# JacdacRHTemp_18.net
KiCad netlist of a schematic drawn in Altium Designer
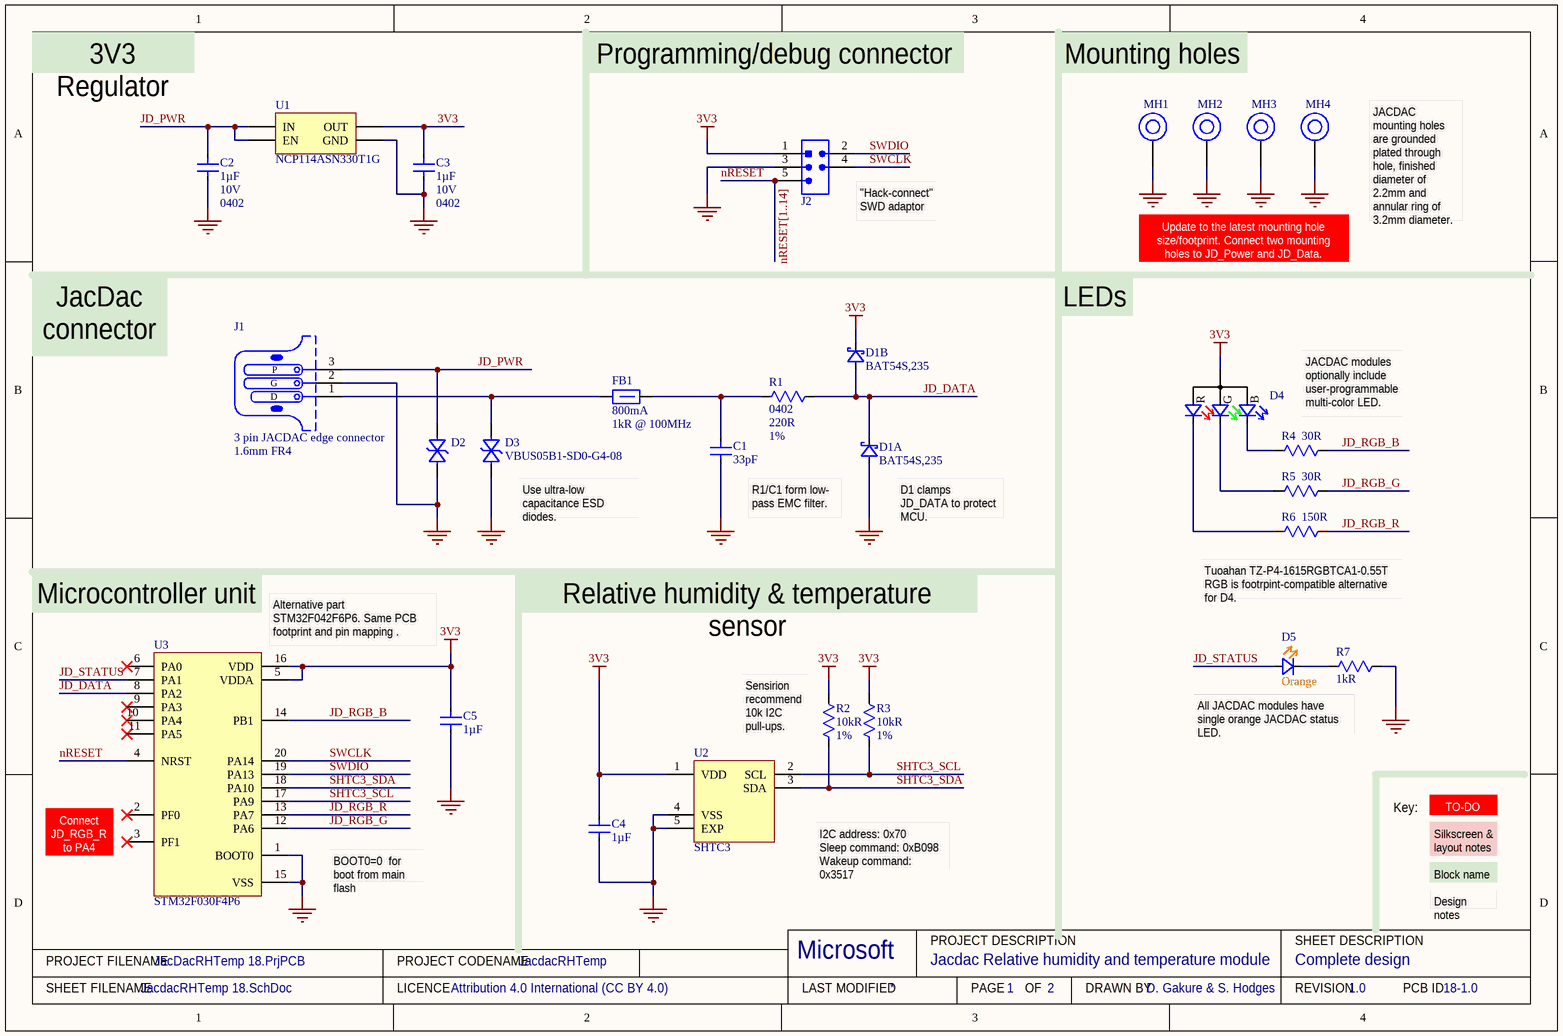
[diagram p0: JacdacRHTemp 18.SchDoc]

(export (version "E")
  (design (tool "Eeschema 10.0.6"))
  (components
    (comp (ref "C1")
      (value "CL05C330JB51PNC")
      (footprint "C0402_0.55MM - without outline")
      (description "CAP CER 33PF 50V NP0 0402")
      (fields
        (field (name "MANUFACTURER") "Samsung")
        (field (name "TOLERANCE") "5%")
        (field (name "CAPACITANCE") "33pF")
        (field (name "CHECKED") "?")
        (field (name "CREATED") "DG")
      )
      (libsource (lib "Samsung") (part "CL05C330JB51PNC"))
    )
    (comp (ref "C2")
      (value "CL05A105KP5NNNC")
      (footprint "C0402_0.55MM - without outline")
      (description "CAP CER 1UF 10V X5R 0402")
      (fields
        (field (name "MANUFACTURER") "Samsung")
        (field (name "TOLERANCE") "10%")
        (field (name "CAPACITANCE") "1µF")
        (field (name "VOLTAGE RATING") "10V")
        (field (name "CASE CODE (IMPERIAL)") "0402")
        (field (name "CREATED") "DG")
        (field (name "CHECKED") "?")
      )
      (libsource (lib "Samsung") (part "CL05A105KP5NNNC"))
    )
    (comp (ref "C3")
      (value "CL05A105KP5NNNC")
      (footprint "C0402_0.55MM - without outline")
      (description "CAP CER 1UF 10V X5R 0402")
      (fields
        (field (name "MANUFACTURER") "Samsung")
        (field (name "TOLERANCE") "10%")
        (field (name "CAPACITANCE") "1µF")
        (field (name "VOLTAGE RATING") "10V")
        (field (name "CASE CODE (IMPERIAL)") "0402")
        (field (name "CREATED") "DG")
        (field (name "CHECKED") "?")
      )
      (libsource (lib "Samsung") (part "CL05A105KP5NNNC"))
    )
    (comp (ref "C4")
      (value "CL05A105KP5NNNC")
      (footprint "C0402_0.55MM - without outline")
      (description "CAP CER 1UF 10V X5R 0402")
      (fields
        (field (name "MANUFACTURER") "Samsung")
        (field (name "TOLERANCE") "10%")
        (field (name "CAPACITANCE") "1µF")
        (field (name "CREATED") "DG")
        (field (name "CHECKED") "?")
      )
      (libsource (lib "Samsung") (part "CL05A105KP5NNNC"))
    )
    (comp (ref "C5")
      (value "CL05A105KP5NNNC")
      (footprint "C0402_0.55MM - without outline")
      (description "CAP CER 1UF 10V X5R 0402")
      (fields
        (field (name "MANUFACTURER") "Samsung")
        (field (name "TOLERANCE") "10%")
        (field (name "CAPACITANCE") "1µF")
        (field (name "CREATED") "DG")
        (field (name "CHECKED") "?")
      )
      (libsource (lib "Samsung") (part "CL05A105KP5NNNC"))
    )
    (comp (ref "D1")
      (value "BAT54S")
      (footprint "NXP-BAT54S-TO-236AB")
      (description "DIODE ARRAY SCHOTTKY 30V SOT23")
      (fields (field (name "MANUFACTURER") "Nexperia") (field (name "MANUFACTURER PART NUMBER") "BAT54S,235"))
      (libsource (lib "NXP") (part "BAT54S"))
    )
    (comp (ref "D2")
      (value "VBUS05B1-SD0-G4-08")
      (footprint "0201-VBUS05B1-SD0-G4-08 - Without outline")
      (description "TVS DIODE 5.5V 18V CLP0603")
      (fields
        (field (name "MANUFACTURER") "Vishay Semiconductors")
        (field (name "CREATED BY") "D. Gakure")
        (field (name "CHECKED BY") "?")
      )
      (libsource (lib "Vishay") (part "VBUS05B1-SD0-G4-08"))
    )
    (comp (ref "D3")
      (value "VBUS05B1-SD0-G4-08")
      (footprint "0201-VBUS05B1-SD0-G4-08 - Without outline")
      (description "TVS DIODE 5.5V 18V CLP0603")
      (fields
        (field (name "MANUFACTURER") "Vishay Semiconductors")
        (field (name "MANUFACTURER PART NUMBER") "VBUS05B1-SD0-G4-08")
        (field (name "CREATED BY") "D. Gakure")
        (field (name "CHECKED BY") "?")
      )
      (libsource (lib "Vishay") (part "VBUS05B1-SD0-G4-08"))
    )
    (comp (ref "D4")
      (value "HSMF-C114")
      (footprint "HSMF-C114")
      (fields
        (field (name "MANUFACTURER") "Broadcom Avago")
        (field (name "CREATED BY") "D. Gakure")
        (field (name "CHECKED BY") "?")
      )
      (libsource (lib "BroadcomLimited") (part "HSMF-C114"))
    )
    (comp (ref "D5")
      (value "SML-D12D")
      (footprint "Rohm SML-D12 Orange - without outline")
      (description "1.6 x 0.8 x 0.55mm (0603) LED 605nm Orange")
      (fields
        (field (name "MANUFACTURER") "Rohm Semiconductor")
        (field (name "MANUFACTURER PART NUMBER") "SML-D12D8WT86")
        (field (name "COLOUR") "Orange")
      )
      (libsource (lib "Rohm") (part "SML-D12D"))
    )
    (comp (ref "FB1")
      (value "TDK MPZ1608S102ATA00")
      (footprint "TDK MPZ1608 0.8mm - without outline")
      (description "0603 1k@100MHz 0.8A chip")
      (fields
        (field (name "TOLERANCE") "25%")
        (field (name "MANUFACTURER") "TDK")
        (field (name "CURRENT RATING") "800mA")
        (field (name "IMPEDANCE") "1kR @ 100MHz")
      )
      (libsource (lib "TDK") (part "TDK MPZ1608S102ATA00"))
    )
    (comp (ref "J1")
      (value "3 pin JACDAC edge connector")
      (footprint "JACDAC_EDGE_CONNECTOR_9.15MM_PCB_WIDE _without_MH")
      (description "3 pin JACDAC edge connector 1.27mm pitch")
      (fields
        (field (name "MANUFACTURER PART NUMBER") "JACDAC_EDGE_CONNECTOR")
        (field (name "PCB TYPE") "1.6mm FR4")
        (field (name "CHECKED BY") "?")
        (field (name "CREATED BY") "D. Gakure")
      )
      (libsource (lib "generic-con") (part "JACDAC edge connector"))
    )
    (comp (ref "J2")
      (value "Hack Connect Mini 1.27 mm pitch 2-row")
      (footprint "HACK_CONNECT_MINI_5_X_1_27")
      (libsource (lib "generic-con") (part "HACK_CONNECT_MINI"))
    )
    (comp (ref "MH1")
      (value "MH_3.9MMNC_2.2MMD")
      (footprint "MH_3.9MMC_2.2MMD_FULL_CIRCLE")
      (description "Mounting Hole 3.9mm Diameter with 3.2 annualar ring, 2.2mm Drill PTH")
      (libsource (lib "generic-con") (part "MH_3.9MMNC_2.2MMD_FULL_CIR"))
    )
    (comp (ref "MH2")
      (value "MH_3.9MMNC_2.2MMD")
      (footprint "MH_3.9MMC_2.2MMD_FULL_CIRCLE")
      (description "Mounting Hole 3.9mm Diameter with 3.2 annualar ring, 2.2mm Drill PTH")
      (libsource (lib "generic-con") (part "MH_3.9MMNC_2.2MMD_FULL_CIR"))
    )
    (comp (ref "MH3")
      (value "MH_3.9MMNC_2.2MMD")
      (footprint "MH_3.9MMC_2.2MMD_FULL_CIRCLE")
      (description "Mounting Hole 3.9mm Diameter with 3.2 annualar ring, 2.2mm Drill PTH")
      (libsource (lib "generic-con") (part "MH_3.9MMNC_2.2MMD_FULL_CIR"))
    )
    (comp (ref "MH4")
      (value "MH_3.9MMNC_2.2MMD")
      (footprint "MH_3.9MMC_2.2MMD_FULL_CIRCLE")
      (description "Mounting Hole 3.9mm Diameter with 3.2 annualar ring, 2.2mm Drill PTH")
      (libsource (lib "generic-con") (part "MH_3.9MMNC_2.2MMD_FULL_CIR"))
    )
    (comp (ref "R1")
      (value "RC0402FR-07220RL")
      (footprint "R0402 - Without outline")
      (description "RES SMD 220 OHM 1% 1/16W 0402")
      (fields
        (field (name "MANUFACTURER") "Yageo")
        (field (name "CASE CODE (IMPERIAL)") "0402")
        (field (name "RESISTANCE") "220R")
        (field (name "TOLERANCE") "1%")
        (field (name "CREATED") "D.G")
        (field (name "CHECKED") "?")
      )
      (libsource (lib "Yageo") (part "RC0402FR-07220RL"))
    )
    (comp (ref "R2")
      (value "10k")
      (footprint "R0402 - Without outline")
      (description "RES SMD 10K OHM 1% 1/16W 0402")
      (fields
        (field (name "MANUFACTURER") "Yageo")
        (field (name "MANUFACTURER PART NUMBER") "RC0402FR-0710KL")
        (field (name "RESISTANCE") "10kR")
        (field (name "TOLERANCE") "1%")
        (field (name "CHECKED") "?")
        (field (name "CREATED") "DG")
      )
      (libsource (lib "Yageo") (part "RC0402FR-0710KL"))
    )
    (comp (ref "R3")
      (value "10k")
      (footprint "R0402 - Without outline")
      (description "RES SMD 10K OHM 1% 1/16W 0402")
      (fields
        (field (name "MANUFACTURER") "Yageo")
        (field (name "MANUFACTURER PART NUMBER") "RC0402FR-0710KL")
        (field (name "RESISTANCE") "10kR")
        (field (name "TOLERANCE") "1%")
        (field (name "CHECKED") "?")
        (field (name "CREATED") "DG")
      )
      (libsource (lib "Yageo") (part "RC0402FR-0710KL"))
    )
    (comp (ref "R4")
      (value "RC0402FR-0730RL")
      (footprint "R0402 - Without outline")
      (description "RES SMD 30 OHM 1% 1/16W 0402")
      (fields
        (field (name "MANUFACTURER") "Yageo")
        (field (name "RESISTANCE") "30R")
        (field (name "TOLERANCE") "1%")
        (field (name "CREATED BY") "D. Gakure")
        (field (name "CHECKED BY") "?")
      )
      (libsource (lib "Yageo") (part "RC0402FR-0730RL"))
    )
    (comp (ref "R5")
      (value "RC0402FR-0730RL")
      (footprint "R0402 - Without outline")
      (description "RES SMD 30 OHM 1% 1/16W 0402")
      (fields
        (field (name "MANUFACTURER") "Yageo")
        (field (name "RESISTANCE") "30R")
        (field (name "TOLERANCE") "1%")
        (field (name "CREATED BY") "D. Gakure")
        (field (name "CHECKED BY") "?")
      )
      (libsource (lib "Yageo") (part "RC0402FR-0730RL"))
    )
    (comp (ref "R6")
      (value "RC0402FR-07150RL")
      (footprint "R0402 - Without outline")
      (description "RES SMD 150 OHM 1% 1/16W 0402")
      (fields
        (field (name "MANUFACTURER") "Yageo")
        (field (name "RESISTANCE") "150R")
        (field (name "TOLERANCE") "1%")
        (field (name "CREATED BY") "D. Gakure")
        (field (name "CHECKED BY") "?")
      )
      (libsource (lib "Yageo") (part "RC0402FR-07150RL"))
    )
    (comp (ref "R7")
      (value "RC0402FR-071KL")
      (footprint "R0402 - Without outline")
      (description "RES SMD 1K OHM 1% 1/16W 0402")
      (fields
        (field (name "MANUFACTURER") "Yageo")
        (field (name "TOLERANCE") "1%")
        (field (name "RESISTANCE") "1kR")
        (field (name "CREATED") "D.G")
        (field (name "CHECKED") "?")
      )
      (libsource (lib "Yageo") (part "RC0402FR-071KL"))
    )
    (comp (ref "U1")
      (value "LDO 3.3V/300 mA")
      (footprint "ON_SEMI-SOT23-5")
      (fields
        (field (name "MANUFACTURER") "ON Semiconductor")
        (field (name "MANUFACTURER PART NUMBER") "NCP114ASN330T1G")
        (field (name "CREATED") "DG")
        (field (name "CHECKED") "?")
      )
      (libsource (lib "OnSemiconductor") (part "NCP114ASN330T1G"))
    )
    (comp (ref "U2")
      (value "SHTC3")
      (footprint "SHTC3_4_WDFN")
      (description "Humidity Temperature Sensor 0 ~ 100% RH I²C ±2% RH 8s Surface Mount")
      (fields
        (field (name "MANUFACTURER") "Sensirion")
        (field (name "MANUFACTURER PART NUMBER") "SHTC3")
        (field (name "CREATED BY") "D. Gakure")
        (field (name "CHECKED BY") "?")
      )
      (libsource (lib "Sensirion") (part "SHTC3"))
    )
    (comp (ref "U3")
      (value "STM32F030F4P6")
      (footprint "20-TSSOP")
      (fields
        (field (name "MANUFACTURER") "STMicroelectronics")
        (field (name "MANUFACTURER PART NUMBER") "STM32F030F4P6")
        (field (name "CREATED") "DG")
        (field (name "CHECKED") "?")
      )
      (libsource (lib "ST") (part "ST STM32F030F4P6"))
    )
  )
  (nets
    (net (code "1") (name "/JD_DATA") (class "Default")
      (node (ref "D1") (pin "3") (pinfunction "K_3") (pintype "passive"))
      (node (ref "R1") (pin "1") (pinfunction "1_1") (pintype "passive"))
      (node (ref "U3") (pin "8") (pinfunction "PA2_8") (pintype "passive"))
    )
    (net (code "2") (name "/JD_PWR") (class "Default")
      (node (ref "C2") (pin "2") (pinfunction "2_2") (pintype "passive"))
      (node (ref "D2") (pin "1") (pinfunction "K_1") (pintype "passive"))
      (node (ref "J1") (pin "3") (pinfunction "P_3") (pintype "passive"))
      (node (ref "U1") (pin "1") (pinfunction "IN_1") (pintype "passive"))
      (node (ref "U1") (pin "3") (pinfunction "EN_3") (pintype "passive"))
    )
    (net (code "3") (name "/JD_RGB_B") (class "Default")
      (node (ref "R4") (pin "2") (pinfunction "2_2") (pintype "passive"))
      (node (ref "U3") (pin "14") (pinfunction "PB1_14") (pintype "passive"))
    )
    (net (code "4") (name "/JD_RGB_G") (class "Default")
      (node (ref "R5") (pin "2") (pinfunction "2_2") (pintype "passive"))
      (node (ref "U3") (pin "12") (pinfunction "PA6_12") (pintype "passive"))
    )
    (net (code "5") (name "/JD_RGB_R") (class "Default")
      (node (ref "R6") (pin "2") (pinfunction "2_2") (pintype "passive"))
      (node (ref "U3") (pin "13") (pinfunction "PA7_13") (pintype "passive"))
    )
    (net (code "6") (name "/JD_STATUS") (class "Default")
      (node (ref "D5") (pin "2") (pinfunction "A_2") (pintype "passive"))
      (node (ref "U3") (pin "7") (pinfunction "PA1_7") (pintype "passive"))
    )
    (net (code "7") (name "/SHTC3_SCL") (class "Default")
      (node (ref "R3") (pin "2") (pinfunction "2_2") (pintype "passive"))
      (node (ref "U2") (pin "2") (pinfunction "SCL_2") (pintype "passive"))
      (node (ref "U3") (pin "17") (pinfunction "PA9_17") (pintype "passive"))
    )
    (net (code "8") (name "/SHTC3_SDA") (class "Default")
      (node (ref "R2") (pin "2") (pinfunction "2_2") (pintype "passive"))
      (node (ref "U2") (pin "3") (pinfunction "SDA_3") (pintype "passive"))
      (node (ref "U3") (pin "18") (pinfunction "PA10_18") (pintype "passive"))
    )
    (net (code "9") (name "/SWCLK") (class "Default")
      (node (ref "J2") (pin "4") (pinfunction "SWCLK_4") (pintype "passive"))
      (node (ref "U3") (pin "20") (pinfunction "PA14_20") (pintype "passive"))
    )
    (net (code "10") (name "/SWDIO") (class "Default")
      (node (ref "J2") (pin "2") (pinfunction "SWDIO_2") (pintype "passive"))
      (node (ref "U3") (pin "19") (pinfunction "PA13_19") (pintype "passive"))
    )
    (net (code "11") (name "/nRESET") (class "Default")
      (node (ref "J2") (pin "5") (pinfunction "RESET_5") (pintype "passive"))
      (node (ref "U3") (pin "4") (pinfunction "NRST_4") (pintype "passive"))
    )
    (net (code "12") (name "3V3") (class "Default")
      (node (ref "C3") (pin "2") (pinfunction "2_2") (pintype "passive"))
      (node (ref "C4") (pin "2") (pinfunction "2_2") (pintype "passive"))
      (node (ref "C5") (pin "2") (pinfunction "2_2") (pintype "passive"))
      (node (ref "D1") (pin "2") (pinfunction "K_2") (pintype "passive"))
      (node (ref "D4") (pin "1") (pinfunction "A_1") (pintype "passive"))
      (node (ref "J2") (pin "1") (pinfunction "VCC_1") (pintype "passive"))
      (node (ref "R2") (pin "1") (pinfunction "1_1") (pintype "passive"))
      (node (ref "R3") (pin "1") (pinfunction "1_1") (pintype "passive"))
      (node (ref "U1") (pin "5") (pinfunction "OUT_5") (pintype "passive"))
      (node (ref "U2") (pin "1") (pinfunction "VDD_1") (pintype "passive"))
      (node (ref "U3") (pin "16") (pinfunction "VDD_16") (pintype "power_in"))
      (node (ref "U3") (pin "5") (pinfunction "VDDA_5") (pintype "power_in"))
    )
    (net (code "13") (name "GND") (class "Default")
      (node (ref "C1") (pin "1") (pinfunction "1_1") (pintype "passive"))
      (node (ref "C2") (pin "1") (pinfunction "1_1") (pintype "passive"))
      (node (ref "C3") (pin "1") (pinfunction "1_1") (pintype "passive"))
      (node (ref "C4") (pin "1") (pinfunction "1_1") (pintype "passive"))
      (node (ref "C5") (pin "1") (pinfunction "1_1") (pintype "passive"))
      (node (ref "D1") (pin "1") (pinfunction "A_1") (pintype "passive"))
      (node (ref "D2") (pin "2") (pinfunction "A_2") (pintype "passive"))
      (node (ref "D3") (pin "2") (pinfunction "A_2") (pintype "passive"))
      (node (ref "J1") (pin "2") (pinfunction "G_2") (pintype "passive"))
      (node (ref "J2") (pin "3") (pinfunction "GND_3") (pintype "passive"))
      (node (ref "MH1") (pin "1") (pinfunction "1_1") (pintype "passive"))
      (node (ref "MH2") (pin "1") (pinfunction "1_1") (pintype "passive"))
      (node (ref "MH3") (pin "1") (pinfunction "1_1") (pintype "passive"))
      (node (ref "MH4") (pin "1") (pinfunction "1_1") (pintype "passive"))
      (node (ref "R7") (pin "1") (pinfunction "1_1") (pintype "passive"))
      (node (ref "U1") (pin "2") (pinfunction "GND_2") (pintype "passive"))
      (node (ref "U2") (pin "4") (pinfunction "VSS_4") (pintype "passive"))
      (node (ref "U2") (pin "5") (pinfunction "EXP_5") (pintype "passive"))
      (node (ref "U3") (pin "1") (pinfunction "BOOT0_1") (pintype "passive"))
      (node (ref "U3") (pin "15") (pinfunction "VSS_15") (pintype "power_in"))
    )
    (net (code "14") (name "Net-(C1-Pad2)") (class "Default")
      (node (ref "C1") (pin "2") (pinfunction "2_2") (pintype "passive"))
      (node (ref "FB1") (pin "2") (pinfunction "2_2") (pintype "passive"))
      (node (ref "R1") (pin "2") (pinfunction "2_2") (pintype "passive"))
    )
    (net (code "15") (name "Net-(D3-K)") (class "Default")
      (node (ref "D3") (pin "1") (pinfunction "K_1") (pintype "passive"))
      (node (ref "FB1") (pin "1") (pinfunction "1_1") (pintype "passive"))
      (node (ref "J1") (pin "1") (pinfunction "D_1") (pintype "passive"))
    )
    (net (code "16") (name "Net-(D4-B)") (class "Default")
      (node (ref "D4") (pin "4") (pinfunction "B_4") (pintype "passive"))
      (node (ref "R4") (pin "1") (pinfunction "1_1") (pintype "passive"))
    )
    (net (code "17") (name "Net-(D4-G)") (class "Default")
      (node (ref "D4") (pin "3") (pinfunction "G_3") (pintype "passive"))
      (node (ref "R5") (pin "1") (pinfunction "1_1") (pintype "passive"))
    )
    (net (code "18") (name "Net-(D4-R)") (class "Default")
      (node (ref "D4") (pin "2") (pinfunction "R_2") (pintype "passive"))
      (node (ref "R6") (pin "1") (pinfunction "1_1") (pintype "passive"))
    )
    (net (code "19") (name "Net-(D5-K)") (class "Default")
      (node (ref "D5") (pin "1") (pinfunction "K_1") (pintype "passive"))
      (node (ref "R7") (pin "2") (pinfunction "2_2") (pintype "passive"))
    )
    (net (code "20") (name "unconnected-(U3-PA0-Pad6)") (class "Default")
      (node (ref "U3") (pin "6") (pinfunction "PA0_6") (pintype "passive+no_connect"))
    )
    (net (code "21") (name "unconnected-(U3-PA3-Pad9)") (class "Default")
      (node (ref "U3") (pin "9") (pinfunction "PA3_9") (pintype "passive+no_connect"))
    )
    (net (code "22") (name "unconnected-(U3-PA4-Pad10)") (class "Default")
      (node (ref "U3") (pin "10") (pinfunction "PA4_10") (pintype "passive+no_connect"))
    )
    (net (code "23") (name "unconnected-(U3-PA5-Pad11)") (class "Default")
      (node (ref "U3") (pin "11") (pinfunction "PA5_11") (pintype "passive+no_connect"))
    )
    (net (code "24") (name "unconnected-(U3-PF0-Pad2)") (class "Default")
      (node (ref "U3") (pin "2") (pinfunction "PF0_2") (pintype "passive+no_connect"))
    )
    (net (code "25") (name "unconnected-(U3-PF1-Pad3)") (class "Default")
      (node (ref "U3") (pin "3") (pinfunction "PF1_3") (pintype "passive+no_connect"))
    )
  )
)
